# sch.net
KiCad netlist of a schematic drawn in Altium Designer
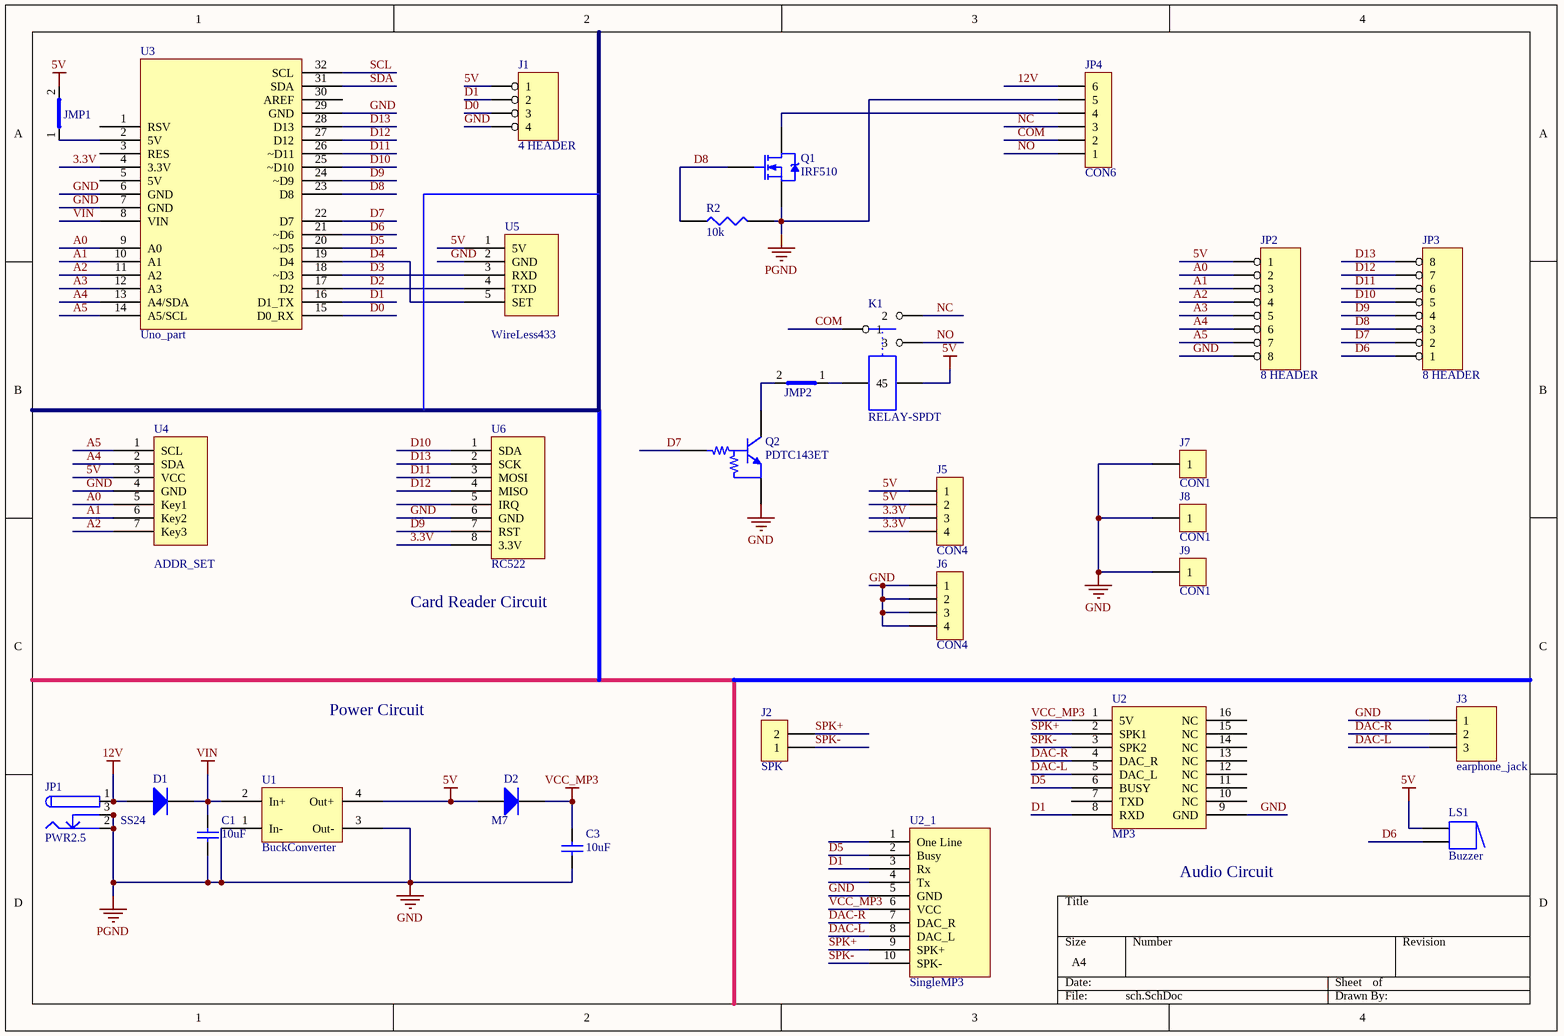
[diagram p0: sch.SchDoc]

(export (version "E")
  (design (tool "Eeschema 10.0.6"))
  (components
    (comp (ref "C1")
      (value "10uF")
      (footprint "1206")
      (description "Capacitor (Semiconductor SIM Model)")
      (fields (field (name "Comment") "Cap Semi") (field (name "PUBLISHER") "Altium Limited"))
      (libsource (lib "Miscellaneous Devices") (part "Cap Semi"))
    )
    (comp (ref "C3")
      (value "10uF")
      (footprint "1206")
      (description "Capacitor (Semiconductor SIM Model)")
      (fields (field (name "Comment") "Cap Semi") (field (name "PUBLISHER") "Altium Limited"))
      (libsource (lib "Miscellaneous Devices") (part "Cap Semi"))
    )
    (comp (ref "D1")
      (value "SS24")
      (footprint "SMB")
      (description "1 Amp General Purpose Rectifier")
      (fields (field (name "PUBLISHER") "Altium Limited"))
      (libsource (lib "Miscellaneous Devices") (part "Diode 1N4001"))
    )
    (comp (ref "D2")
      (value "M7")
      (footprint "SMA")
      (description "1 Amp General Purpose Rectifier")
      (fields (field (name "PUBLISHER") "Altium Limited"))
      (libsource (lib "Miscellaneous Devices") (part "Diode 1N4001"))
    )
    (comp (ref "J1")
      (value "4 HEADER")
      (footprint "HDR1X4")
      (description "4 Pin Header")
      (libsource (lib "Miscellaneous Devices") (part "4 HEADER"))
    )
    (comp (ref "J2") (value "SPK") (footprint "DG1282") (libsource (lib "常用元件库") (part "CON2")))
    (comp (ref "J3")
      (value "earphone_jack")
      (footprint "PcbLib1:Phone-Jack")
      (description "Header, 3-Pin")
      (fields (field (name "PUBLISHER") "Altium Limited"))
      (libsource (lib "Miscellaneous Connectors") (part "Header 3"))
    )
    (comp (ref "J5")
      (value "CON4")
      (footprint "SIP4")
      (description "Connector")
      (libsource (lib "Miscellaneous Devices") (part "CON4"))
    )
    (comp (ref "J6")
      (value "CON4")
      (footprint "SIP4")
      (description "Connector")
      (libsource (lib "Miscellaneous Devices") (part "CON4"))
    )
    (comp (ref "J7") (value "CON1") (footprint "One Pin") (libsource (lib "常用元件库") (part "CON1")))
    (comp (ref "J8") (value "CON1") (footprint "One Pin") (libsource (lib "常用元件库") (part "CON1")))
    (comp (ref "J9") (value "CON1") (footprint "One Pin") (libsource (lib "常用元件库") (part "CON1")))
    (comp (ref "JMP1") (value "JUMPER") (footprint "HDR1X2") (libsource (lib "Schlib") (part "JUMPER")))
    (comp (ref "JMP2") (value "JUMPER") (footprint "HDR1X2") (libsource (lib "Schlib") (part "JUMPER")))
    (comp (ref "JP1")
      (value "PWR2.5")
      (footprint "KLD-0202_new")
      (description "Low Voltage Power Supply Connector")
      (fields (field (name "PUBLISHER") "Altium Limited"))
      (libsource (lib "Miscellaneous Connectors") (part "PWR2.5"))
    )
    (comp (ref "JP2")
      (value "8 HEADER")
      (footprint "POWER CONN8")
      (description "8 Pin Header")
      (libsource (lib "Miscellaneous Devices") (part "8 HEADER"))
    )
    (comp (ref "JP3")
      (value "8 HEADER")
      (footprint "POWER CONN8")
      (description "8 Pin Header")
      (libsource (lib "") (part "8 HEADER_1"))
    )
    (comp (ref "JP4")
      (value "CON6")
      (footprint "PcbLib1:POWER CONN6")
      (description "Connector")
      (libsource (lib "Miscellaneous Devices") (part "CON6"))
    )
    (comp (ref "K1")
      (value "RELAY-SPDT")
      (footprint "RELAY_SPDT")
      (libsource (lib "Miscellaneous Devices") (part "RELAY-SPDT"))
    )
    (comp (ref "LS1")
      (value "Buzzer")
      (footprint "BUZZ")
      (description "Magnetic Transducer Buzzer")
      (fields (field (name "PUBLISHER") "Altium Limited"))
      (libsource (lib "Miscellaneous Devices") (part "Buzzer"))
    )
    (comp (ref "Q1")
      (value "IRF510")
      (footprint "常用元件封装:TO-220")
      (description "HEXFET N-Channel Power MOSFET")
      (fields (field (name "PUBLISHER") "Altium Limited"))
      (libsource (lib "IR Discrete MOSFET - Power") (part "IRF510"))
    )
    (comp (ref "Q2")
      (value "PDTC143ET")
      (footprint "SOT23")
      (description "NPN Resistor-equipped Transistor")
      (fields (field (name "PUBLISHER") "Altium Limited"))
      (libsource (lib "Philips Discrete BJT - Low Power") (part "PDTC143ET"))
    )
    (comp (ref "R2") (value "10k") (footprint "1206") (libsource (lib "Miscellaneous Devices") (part "RES1")))
    (comp (ref "U1")
      (value "BuckConverter")
      (footprint "BuckConverter")
      (libsource (lib "Schlib") (part "BuckConverter"))
    )
    (comp (ref "U2") (value "MP3") (footprint "MP3") (libsource (lib "Schlib") (part "MP3")))
    (comp (ref "U2_1")
      (value "SingleMP3")
      (footprint "HDR1X10")
      (libsource (lib "Schlib") (part "SingleMP3"))
    )
    (comp (ref "U3") (value "Uno_part") (footprint "UNO") (libsource (lib "Schlib") (part "Uno_part")))
    (comp (ref "U4")
      (value "ADDR_SET")
      (footprint "Miscellaneous Connectors:HDR1X7")
      (libsource (lib "Schlib") (part "ADDR_SET"))
    )
    (comp (ref "U5")
      (value "WireLess433")
      (footprint "Miscellaneous Connectors:HDR1X5")
      (libsource (lib "Schlib") (part "WireLess433"))
    )
    (comp (ref "U6")
      (value "RC522")
      (footprint "Miscellaneous Connectors:HDR1X8")
      (libsource (lib "Schlib") (part "RC522"))
    )
  )
  (nets
    (net (code "1") (name "/3.3V") (class "Default")
      (node (ref "J5") (pin "3") (pinfunction "3_3") (pintype "passive"))
      (node (ref "J5") (pin "4") (pinfunction "4_4") (pintype "passive"))
      (node (ref "U3") (pin "4") (pinfunction "3.3V_4") (pintype "passive"))
      (node (ref "U6") (pin "8") (pinfunction "3.3V_8") (pintype "passive"))
    )
    (net (code "2") (name "/A0") (class "Default")
      (node (ref "JP2") (pin "2") (pinfunction "2_2") (pintype "passive"))
      (node (ref "U3") (pin "9") (pinfunction "A0_9") (pintype "passive"))
      (node (ref "U4") (pin "5") (pinfunction "Key1_5") (pintype "passive"))
    )
    (net (code "3") (name "/A1") (class "Default")
      (node (ref "JP2") (pin "3") (pinfunction "3_3") (pintype "passive"))
      (node (ref "U3") (pin "10") (pinfunction "A1_10") (pintype "passive"))
      (node (ref "U4") (pin "6") (pinfunction "Key2_6") (pintype "passive"))
    )
    (net (code "4") (name "/A2") (class "Default")
      (node (ref "JP2") (pin "4") (pinfunction "4_4") (pintype "passive"))
      (node (ref "U3") (pin "11") (pinfunction "A2_11") (pintype "passive"))
      (node (ref "U4") (pin "7") (pinfunction "Key3_7") (pintype "passive"))
    )
    (net (code "5") (name "/A3") (class "Default")
      (node (ref "JP2") (pin "5") (pinfunction "5_5") (pintype "passive"))
      (node (ref "U3") (pin "12") (pinfunction "A3_12") (pintype "passive"))
    )
    (net (code "6") (name "/A4") (class "Default")
      (node (ref "JP2") (pin "6") (pinfunction "6_6") (pintype "passive"))
      (node (ref "U3") (pin "13") (pinfunction "A4/SDA_13") (pintype "passive"))
      (node (ref "U4") (pin "2") (pinfunction "SDA_2") (pintype "passive"))
    )
    (net (code "7") (name "/A5") (class "Default")
      (node (ref "JP2") (pin "7") (pinfunction "7_7") (pintype "passive"))
      (node (ref "U3") (pin "14") (pinfunction "A5/SCL_14") (pintype "passive"))
      (node (ref "U4") (pin "1") (pinfunction "SCL_1") (pintype "passive"))
    )
    (net (code "8") (name "/COM") (class "Default")
      (node (ref "JP4") (pin "2") (pinfunction "2_2") (pintype "passive"))
      (node (ref "K1") (pin "1") (pinfunction "1_1") (pintype "passive"))
    )
    (net (code "9") (name "/D0") (class "Default")
      (node (ref "J1") (pin "3") (pinfunction "3_3") (pintype "passive"))
      (node (ref "U3") (pin "15") (pinfunction "D0_RX_15") (pintype "passive"))
    )
    (net (code "10") (name "/D1") (class "Default")
      (node (ref "J1") (pin "2") (pinfunction "2_2") (pintype "passive"))
      (node (ref "U2") (pin "8") (pinfunction "RXD_8") (pintype "passive"))
      (node (ref "U2_1") (pin "3") (pinfunction "Rx_3") (pintype "passive"))
      (node (ref "U3") (pin "16") (pinfunction "D1_TX_16") (pintype "passive"))
    )
    (net (code "11") (name "/D2") (class "Default")
      (node (ref "U3") (pin "17") (pinfunction "D2_17") (pintype "passive"))
      (node (ref "U5") (pin "4") (pinfunction "TXD_4") (pintype "passive"))
    )
    (net (code "12") (name "/D3") (class "Default")
      (node (ref "U3") (pin "18") (pinfunction "~D3_18") (pintype "passive"))
      (node (ref "U5") (pin "3") (pinfunction "RXD_3") (pintype "passive"))
    )
    (net (code "13") (name "/D4") (class "Default")
      (node (ref "U3") (pin "19") (pinfunction "D4_19") (pintype "passive"))
      (node (ref "U5") (pin "5") (pinfunction "SET_5") (pintype "passive"))
    )
    (net (code "14") (name "/D5") (class "Default")
      (node (ref "U2") (pin "6") (pinfunction "BUSY_6") (pintype "passive"))
      (node (ref "U2_1") (pin "2") (pinfunction "Busy_2") (pintype "passive"))
      (node (ref "U3") (pin "20") (pinfunction "~D5_20") (pintype "passive"))
    )
    (net (code "15") (name "/D6") (class "Default")
      (node (ref "JP3") (pin "1") (pinfunction "1_1") (pintype "passive"))
      (node (ref "LS1") (pin "2") (pinfunction "2_2") (pintype "passive"))
      (node (ref "U3") (pin "21") (pinfunction "~D6_21") (pintype "passive"))
    )
    (net (code "16") (name "/D7") (class "Default")
      (node (ref "JP3") (pin "2") (pinfunction "2_2") (pintype "passive"))
      (node (ref "Q2") (pin "1") (pinfunction "B_1") (pintype "passive"))
      (node (ref "U3") (pin "22") (pinfunction "D7_22") (pintype "passive"))
    )
    (net (code "17") (name "/D8") (class "Default")
      (node (ref "JP3") (pin "3") (pinfunction "3_3") (pintype "passive"))
      (node (ref "Q1") (pin "1") (pinfunction "G_1") (pintype "passive"))
      (node (ref "R2") (pin "1") (pinfunction "1_1") (pintype "passive"))
      (node (ref "U3") (pin "23") (pinfunction "D8_23") (pintype "passive"))
    )
    (net (code "18") (name "/D9") (class "Default")
      (node (ref "JP3") (pin "4") (pinfunction "4_4") (pintype "passive"))
      (node (ref "U3") (pin "24") (pinfunction "~D9_24") (pintype "passive"))
      (node (ref "U6") (pin "7") (pinfunction "RST_7") (pintype "passive"))
    )
    (net (code "19") (name "/D10") (class "Default")
      (node (ref "JP3") (pin "5") (pinfunction "5_5") (pintype "passive"))
      (node (ref "U3") (pin "25") (pinfunction "~D10_25") (pintype "passive"))
      (node (ref "U6") (pin "1") (pinfunction "SDA_1") (pintype "passive"))
    )
    (net (code "20") (name "/D11") (class "Default")
      (node (ref "JP3") (pin "6") (pinfunction "6_6") (pintype "passive"))
      (node (ref "U3") (pin "26") (pinfunction "~D11_26") (pintype "passive"))
      (node (ref "U6") (pin "3") (pinfunction "MOSI_3") (pintype "passive"))
    )
    (net (code "21") (name "/D12") (class "Default")
      (node (ref "JP3") (pin "7") (pinfunction "7_7") (pintype "passive"))
      (node (ref "U3") (pin "27") (pinfunction "D12_27") (pintype "passive"))
      (node (ref "U6") (pin "4") (pinfunction "MISO_4") (pintype "passive"))
    )
    (net (code "22") (name "/D13") (class "Default")
      (node (ref "JP3") (pin "8") (pinfunction "8_8") (pintype "passive"))
      (node (ref "U3") (pin "28") (pinfunction "D13_28") (pintype "passive"))
      (node (ref "U6") (pin "2") (pinfunction "SCK_2") (pintype "passive"))
    )
    (net (code "23") (name "/DAC-L") (class "Default")
      (node (ref "J3") (pin "3") (pinfunction "3_3") (pintype "passive"))
      (node (ref "U2") (pin "5") (pinfunction "DAC_L_5") (pintype "passive"))
      (node (ref "U2_1") (pin "8") (pinfunction "DAC_L_8") (pintype "passive"))
    )
    (net (code "24") (name "/DAC-R") (class "Default")
      (node (ref "J3") (pin "2") (pinfunction "2_2") (pintype "passive"))
      (node (ref "U2") (pin "4") (pinfunction "DAC_R_4") (pintype "passive"))
      (node (ref "U2_1") (pin "7") (pinfunction "DAC_R_7") (pintype "passive"))
    )
    (net (code "25") (name "/NC") (class "Default")
      (node (ref "JP4") (pin "3") (pinfunction "3_3") (pintype "passive"))
      (node (ref "K1") (pin "2") (pinfunction "2_2") (pintype "passive"))
    )
    (net (code "26") (name "/NO") (class "Default")
      (node (ref "JP4") (pin "1") (pinfunction "1_1") (pintype "passive"))
      (node (ref "K1") (pin "3") (pinfunction "3_3") (pintype "passive"))
    )
    (net (code "27") (name "/SCL") (class "Default")
      (node (ref "U3") (pin "32") (pinfunction "SCL_32") (pintype "passive"))
    )
    (net (code "28") (name "/SDA") (class "Default")
      (node (ref "U3") (pin "31") (pinfunction "SDA_31") (pintype "passive"))
    )
    (net (code "29") (name "/SPK+") (class "Default")
      (node (ref "J2") (pin "2") (pinfunction "2_2") (pintype "passive"))
      (node (ref "U2") (pin "2") (pinfunction "SPK1_2") (pintype "passive"))
      (node (ref "U2_1") (pin "9") (pinfunction "SPK+_9") (pintype "passive"))
    )
    (net (code "30") (name "/SPK-") (class "Default")
      (node (ref "J2") (pin "1") (pinfunction "1_1") (pintype "passive"))
      (node (ref "U2") (pin "3") (pinfunction "SPK2_3") (pintype "passive"))
      (node (ref "U2_1") (pin "10") (pinfunction "SPK-_10") (pintype "passive"))
    )
    (net (code "31") (name "5V") (class "Default")
      (node (ref "D2") (pin "A") (pinfunction "A_A") (pintype "passive"))
      (node (ref "J1") (pin "1") (pinfunction "1_1") (pintype "passive"))
      (node (ref "J5") (pin "1") (pinfunction "1_1") (pintype "passive"))
      (node (ref "J5") (pin "2") (pinfunction "2_2") (pintype "passive"))
      (node (ref "JMP1") (pin "2") (pinfunction "O_2") (pintype "passive"))
      (node (ref "JP2") (pin "1") (pinfunction "1_1") (pintype "passive"))
      (node (ref "K1") (pin "5") (pinfunction "5_5") (pintype "passive"))
      (node (ref "LS1") (pin "1") (pinfunction "1_1") (pintype "passive"))
      (node (ref "U1") (pin "4") (pinfunction "Out+_4") (pintype "passive"))
      (node (ref "U4") (pin "3") (pinfunction "VCC_3") (pintype "passive"))
      (node (ref "U5") (pin "1") (pinfunction "5V_1") (pintype "passive"))
    )
    (net (code "32") (name "12V") (class "Default")
      (node (ref "D1") (pin "A") (pinfunction "A_A") (pintype "passive"))
      (node (ref "JP1") (pin "1") (pinfunction "1_1") (pintype "power_in"))
      (node (ref "JP1") (pin "1A") (pinfunction "1A_1A") (pintype "power_in"))
      (node (ref "JP1") (pin "1B") (pinfunction "1B_1B") (pintype "power_in"))
      (node (ref "JP4") (pin "6") (pinfunction "6_6") (pintype "passive"))
    )
    (net (code "33") (name "GND") (class "Default")
      (node (ref "C1") (pin "1") (pinfunction "1_1") (pintype "passive"))
      (node (ref "C3") (pin "1") (pinfunction "1_1") (pintype "passive"))
      (node (ref "J1") (pin "4") (pinfunction "4_4") (pintype "passive"))
      (node (ref "J3") (pin "1") (pinfunction "1_1") (pintype "passive"))
      (node (ref "J6") (pin "1") (pinfunction "1_1") (pintype "passive"))
      (node (ref "J6") (pin "2") (pinfunction "2_2") (pintype "passive"))
      (node (ref "J6") (pin "3") (pinfunction "3_3") (pintype "passive"))
      (node (ref "J6") (pin "4") (pinfunction "4_4") (pintype "passive"))
      (node (ref "J7") (pin "1") (pinfunction "1_1") (pintype "passive"))
      (node (ref "J8") (pin "1") (pinfunction "1_1") (pintype "passive"))
      (node (ref "J9") (pin "1") (pinfunction "1_1") (pintype "passive"))
      (node (ref "JP1") (pin "2") (pinfunction "2_2") (pintype "power_in"))
      (node (ref "JP1") (pin "2A") (pinfunction "2A_2A") (pintype "power_in"))
      (node (ref "JP1") (pin "2B") (pinfunction "2B_2B") (pintype "power_in"))
      (node (ref "JP1") (pin "3") (pinfunction "3_3") (pintype "power_in"))
      (node (ref "JP1") (pin "3A") (pinfunction "3A_3A") (pintype "power_in"))
      (node (ref "JP1") (pin "3B") (pinfunction "3B_3B") (pintype "power_in"))
      (node (ref "JP2") (pin "8") (pinfunction "8_8") (pintype "passive"))
      (node (ref "JP4") (pin "5") (pinfunction "5_5") (pintype "passive"))
      (node (ref "Q1") (pin "3") (pinfunction "S_3") (pintype "passive"))
      (node (ref "Q2") (pin "2") (pinfunction "E_2") (pintype "passive"))
      (node (ref "R2") (pin "2") (pinfunction "2_2") (pintype "passive"))
      (node (ref "U1") (pin "1") (pinfunction "In-_1") (pintype "passive"))
      (node (ref "U1") (pin "3") (pinfunction "Out-_3") (pintype "passive"))
      (node (ref "U2") (pin "9") (pinfunction "GND_9") (pintype "passive"))
      (node (ref "U2_1") (pin "5") (pinfunction "GND_5") (pintype "passive"))
      (node (ref "U3") (pin "29") (pinfunction "GND_29") (pintype "passive"))
      (node (ref "U3") (pin "6") (pinfunction "GND_6") (pintype "passive"))
      (node (ref "U3") (pin "7") (pinfunction "GND_7") (pintype "passive"))
      (node (ref "U4") (pin "4") (pinfunction "GND_4") (pintype "passive"))
      (node (ref "U5") (pin "2") (pinfunction "GND_2") (pintype "passive"))
      (node (ref "U6") (pin "6") (pinfunction "GND_6") (pintype "passive"))
    )
    (net (code "34") (name "Net-(JMP1-I)") (class "Default")
      (node (ref "JMP1") (pin "1") (pinfunction "I_1") (pintype "passive"))
      (node (ref "U3") (pin "2") (pinfunction "5V_2") (pintype "passive"))
    )
    (net (code "35") (name "Net-(JMP2-I)") (class "Default")
      (node (ref "JMP2") (pin "1") (pinfunction "I_1") (pintype "passive"))
      (node (ref "K1") (pin "4") (pinfunction "4_4") (pintype "passive"))
    )
    (net (code "36") (name "Net-(JMP2-O)") (class "Default")
      (node (ref "JMP2") (pin "2") (pinfunction "O_2") (pintype "passive"))
      (node (ref "Q2") (pin "3") (pinfunction "C_3") (pintype "passive"))
    )
    (net (code "37") (name "Net-(Q1-D)") (class "Default")
      (node (ref "JP4") (pin "4") (pinfunction "4_4") (pintype "passive"))
      (node (ref "Q1") (pin "2") (pinfunction "D_2") (pintype "passive"))
    )
    (net (code "38") (name "VCC_MP3") (class "Default")
      (node (ref "C3") (pin "2") (pinfunction "2_2") (pintype "passive"))
      (node (ref "D2") (pin "K") (pinfunction "K_K") (pintype "passive"))
      (node (ref "U2") (pin "1") (pinfunction "5V_1") (pintype "passive"))
      (node (ref "U2_1") (pin "6") (pinfunction "VCC_6") (pintype "passive"))
    )
    (net (code "39") (name "VIN") (class "Default")
      (node (ref "C1") (pin "2") (pinfunction "2_2") (pintype "passive"))
      (node (ref "D1") (pin "K") (pinfunction "K_K") (pintype "passive"))
      (node (ref "U1") (pin "2") (pinfunction "In+_2") (pintype "passive"))
      (node (ref "U3") (pin "8") (pinfunction "VIN_8") (pintype "passive"))
    )
    (net (code "40") (name "unconnected-(U2-NC-Pad10)") (class "Default")
      (node (ref "U2") (pin "10") (pinfunction "NC_10") (pintype "passive"))
    )
    (net (code "41") (name "unconnected-(U2-NC-Pad11)") (class "Default")
      (node (ref "U2") (pin "11") (pinfunction "NC_11") (pintype "passive"))
    )
    (net (code "42") (name "unconnected-(U2-NC-Pad12)") (class "Default")
      (node (ref "U2") (pin "12") (pinfunction "NC_12") (pintype "passive"))
    )
    (net (code "43") (name "unconnected-(U2-NC-Pad13)") (class "Default")
      (node (ref "U2") (pin "13") (pinfunction "NC_13") (pintype "passive"))
    )
    (net (code "44") (name "unconnected-(U2-NC-Pad14)") (class "Default")
      (node (ref "U2") (pin "14") (pinfunction "NC_14") (pintype "passive"))
    )
    (net (code "45") (name "unconnected-(U2-NC-Pad15)") (class "Default")
      (node (ref "U2") (pin "15") (pinfunction "NC_15") (pintype "passive"))
    )
    (net (code "46") (name "unconnected-(U2-NC-Pad16)") (class "Default")
      (node (ref "U2") (pin "16") (pinfunction "NC_16") (pintype "passive"))
    )
    (net (code "47") (name "unconnected-(U2-TXD-Pad7)") (class "Default")
      (node (ref "U2") (pin "7") (pinfunction "TXD_7") (pintype "passive"))
    )
    (net (code "48") (name "unconnected-(U2_1-One_Line-Pad1)") (class "Default")
      (node (ref "U2_1") (pin "1") (pinfunction "One_Line_1") (pintype "passive"))
    )
    (net (code "49") (name "unconnected-(U2_1-Tx-Pad4)") (class "Default")
      (node (ref "U2_1") (pin "4") (pinfunction "Tx_4") (pintype "passive"))
    )
    (net (code "50") (name "unconnected-(U3-5V-Pad5)") (class "Default")
      (node (ref "U3") (pin "5") (pinfunction "5V_5") (pintype "passive"))
    )
    (net (code "51") (name "unconnected-(U3-AREF-Pad30)") (class "Default")
      (node (ref "U3") (pin "30") (pinfunction "AREF_30") (pintype "passive"))
    )
    (net (code "52") (name "unconnected-(U3-RES-Pad3)") (class "Default")
      (node (ref "U3") (pin "3") (pinfunction "RES_3") (pintype "passive"))
    )
    (net (code "53") (name "unconnected-(U3-RSV-Pad1)") (class "Default")
      (node (ref "U3") (pin "1") (pinfunction "RSV_1") (pintype "passive"))
    )
    (net (code "54") (name "unconnected-(U6-IRQ-Pad5)") (class "Default")
      (node (ref "U6") (pin "5") (pinfunction "IRQ_5") (pintype "passive"))
    )
  )
)
